# voltage_conditioner.net
KiCad netlist of a schematic drawn in EAGLE
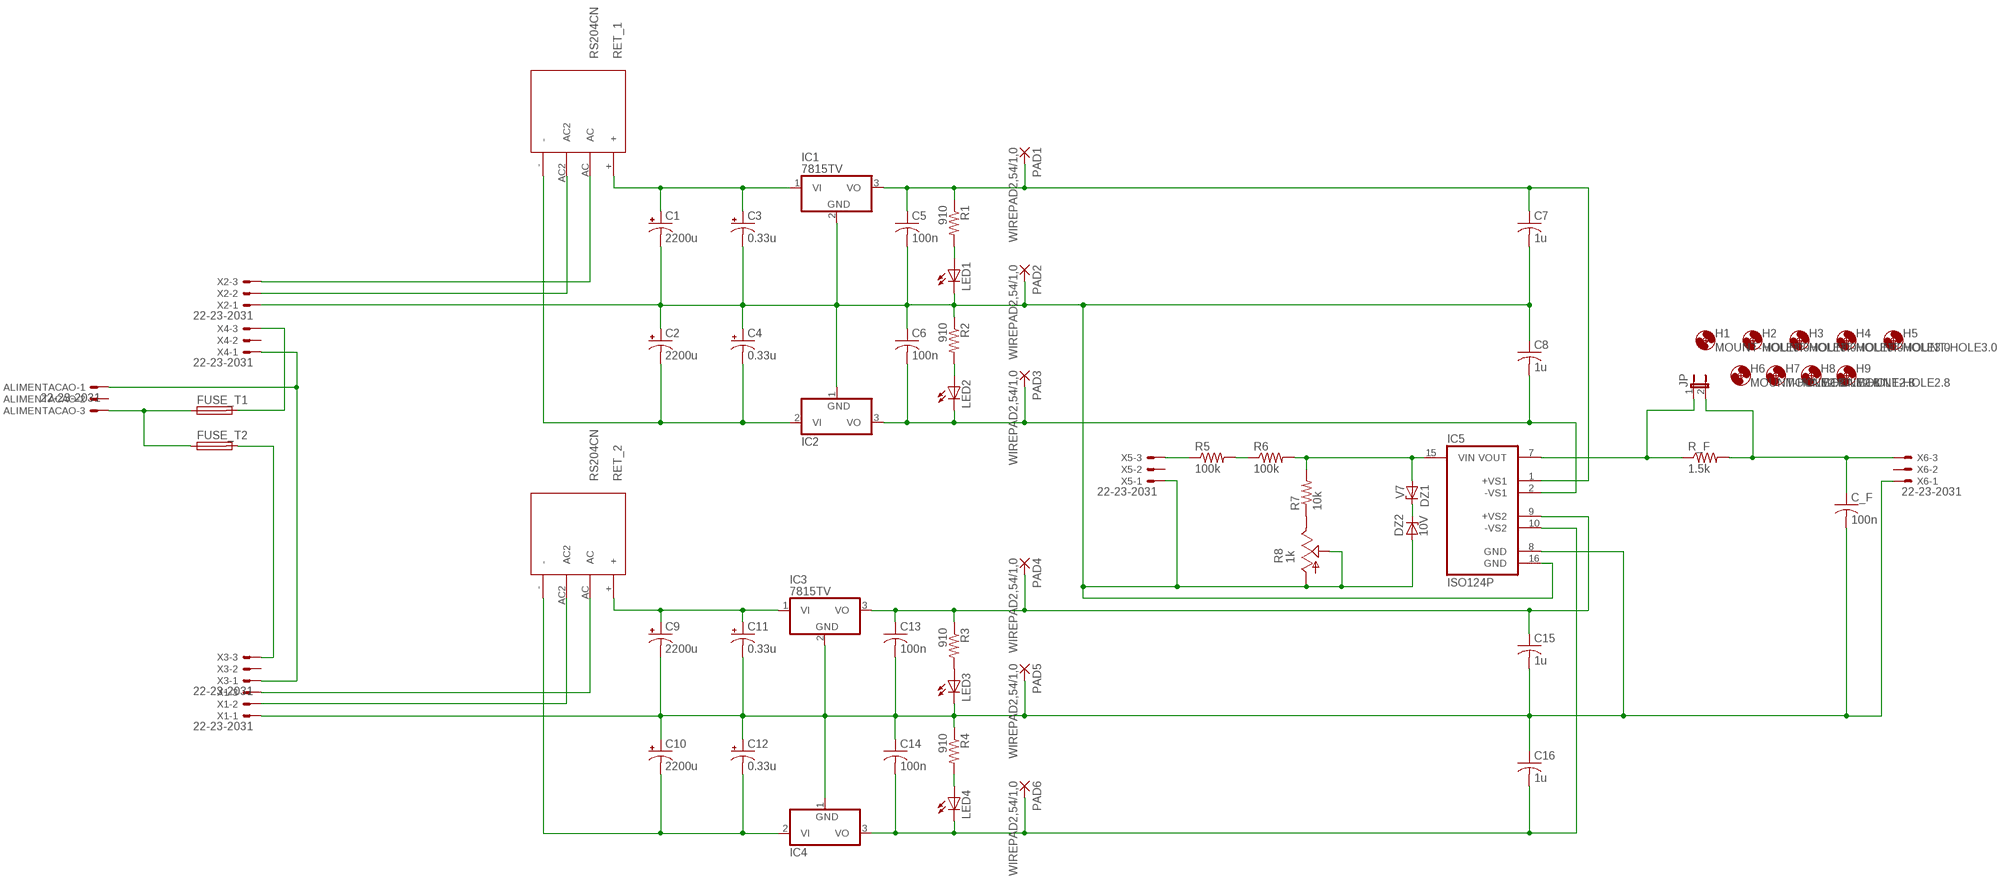
[diagram p0: schematic, sheet 1]

(export (version "E")
  (design (tool "Eeschema 10.0.6"))
  (components
    (comp (ref "ALIMENTACAO")
      (value "22-23-2031")
      (footprint "eagle-import:22-23-2031")
      (fields (field (name "MF") "MOLEX"))
      (libsource (lib "eagle-import") (part "22-23-2031"))
    )
    (comp (ref "C1")
      (value "2200u")
      (footprint "eagle-import:E5-10,5")
      (libsource (lib "eagle-import") (part "CPOL-USE5-10.5"))
    )
    (comp (ref "C2")
      (value "2200u")
      (footprint "eagle-import:E5-10,5")
      (libsource (lib "eagle-import") (part "CPOL-USE5-10.5"))
    )
    (comp (ref "C3")
      (value "0.33u")
      (footprint "eagle-import:E2,5-5")
      (libsource (lib "eagle-import") (part "CPOL-USE2.5-5"))
    )
    (comp (ref "C4")
      (value "0.33u")
      (footprint "eagle-import:E2,5-5")
      (libsource (lib "eagle-import") (part "CPOL-USE2.5-5"))
    )
    (comp (ref "C5")
      (value "100n")
      (footprint "eagle-import:C050-025X075")
      (libsource (lib "eagle-import") (part "C-US050-025X075"))
    )
    (comp (ref "C6")
      (value "100n")
      (footprint "eagle-import:C050-025X075")
      (libsource (lib "eagle-import") (part "C-US050-025X075"))
    )
    (comp (ref "C7")
      (value "1u")
      (footprint "eagle-import:C025-025X050")
      (libsource (lib "eagle-import") (part "C-US025-025X050"))
    )
    (comp (ref "C8")
      (value "1u")
      (footprint "eagle-import:C025-025X050")
      (libsource (lib "eagle-import") (part "C-US025-025X050"))
    )
    (comp (ref "C9")
      (value "2200u")
      (footprint "eagle-import:E5-10,5")
      (libsource (lib "eagle-import") (part "CPOL-USE5-10.5"))
    )
    (comp (ref "C10")
      (value "2200u")
      (footprint "eagle-import:E5-10,5")
      (libsource (lib "eagle-import") (part "CPOL-USE5-10.5"))
    )
    (comp (ref "C11")
      (value "0.33u")
      (footprint "eagle-import:E2,5-5")
      (libsource (lib "eagle-import") (part "CPOL-USE2.5-5"))
    )
    (comp (ref "C12")
      (value "0.33u")
      (footprint "eagle-import:E2,5-5")
      (libsource (lib "eagle-import") (part "CPOL-USE2.5-5"))
    )
    (comp (ref "C13")
      (value "100n")
      (footprint "eagle-import:C050-025X075")
      (libsource (lib "eagle-import") (part "C-US050-025X075"))
    )
    (comp (ref "C14")
      (value "100n")
      (footprint "eagle-import:C050-025X075")
      (libsource (lib "eagle-import") (part "C-US050-025X075"))
    )
    (comp (ref "C15")
      (value "1u")
      (footprint "eagle-import:C025-025X050")
      (libsource (lib "eagle-import") (part "C-US025-025X050"))
    )
    (comp (ref "C16")
      (value "1u")
      (footprint "eagle-import:C025-025X050")
      (libsource (lib "eagle-import") (part "C-US025-025X050"))
    )
    (comp (ref "C_F")
      (value "100n")
      (footprint "eagle-import:C050-025X075")
      (libsource (lib "eagle-import") (part "C-US050-025X075"))
    )
    (comp (ref "DZ1")
      (value "V7")
      (footprint "eagle-import:DO35Z10")
      (libsource (lib "eagle-import") (part "ZENER-DIODEDO35Z10"))
    )
    (comp (ref "DZ2")
      (value "10V")
      (footprint "eagle-import:DO35Z10")
      (libsource (lib "eagle-import") (part "ZENER-DIODEDO35Z10"))
    )
    (comp (ref "FUSE_T1")
      (value "GSH15")
      (footprint "eagle-import:GSH15")
      (fields (field (name "MPN") "64900001039"))
      (libsource (lib "eagle-import") (part "GSH15"))
    )
    (comp (ref "FUSE_T2")
      (value "GSH15")
      (footprint "eagle-import:GSH15")
      (fields (field (name "MPN") "64900001039"))
      (libsource (lib "eagle-import") (part "GSH15"))
    )
    (comp (ref "H1")
      (value "MOUNT-HOLE3.0")
      (footprint "eagle-import:3,0")
      (libsource (lib "eagle-import") (part "MOUNT-HOLE3.0"))
    )
    (comp (ref "H2")
      (value "MOUNT-HOLE3.0")
      (footprint "eagle-import:3,0")
      (libsource (lib "eagle-import") (part "MOUNT-HOLE3.0"))
    )
    (comp (ref "H3")
      (value "MOUNT-HOLE3.0")
      (footprint "eagle-import:3,0")
      (libsource (lib "eagle-import") (part "MOUNT-HOLE3.0"))
    )
    (comp (ref "H4")
      (value "MOUNT-HOLE3.0")
      (footprint "eagle-import:3,0")
      (libsource (lib "eagle-import") (part "MOUNT-HOLE3.0"))
    )
    (comp (ref "H5")
      (value "MOUNT-HOLE3.0")
      (footprint "eagle-import:3,0")
      (libsource (lib "eagle-import") (part "MOUNT-HOLE3.0"))
    )
    (comp (ref "H6")
      (value "MOUNT-HOLE2.8")
      (footprint "eagle-import:2,8")
      (libsource (lib "eagle-import") (part "MOUNT-HOLE2.8"))
    )
    (comp (ref "H7")
      (value "MOUNT-HOLE2.8")
      (footprint "eagle-import:2,8")
      (libsource (lib "eagle-import") (part "MOUNT-HOLE2.8"))
    )
    (comp (ref "H8")
      (value "MOUNT-HOLE2.8")
      (footprint "eagle-import:2,8")
      (libsource (lib "eagle-import") (part "MOUNT-HOLE2.8"))
    )
    (comp (ref "H9")
      (value "MOUNT-HOLE2.8")
      (footprint "eagle-import:2,8")
      (libsource (lib "eagle-import") (part "MOUNT-HOLE2.8"))
    )
    (comp (ref "IC1")
      (value "7815TV")
      (footprint "eagle-import:TO220V")
      (libsource (lib "eagle-import") (part "78TV15"))
    )
    (comp (ref "IC2")
      (value "7915C")
      (footprint "eagle-import:TO220V")
      (libsource (lib "eagle-import") (part "7915C"))
    )
    (comp (ref "IC3")
      (value "7815TV")
      (footprint "eagle-import:TO220V")
      (libsource (lib "eagle-import") (part "78TV15"))
    )
    (comp (ref "IC4")
      (value "7915C")
      (footprint "eagle-import:TO220V")
      (libsource (lib "eagle-import") (part "7915C"))
    )
    (comp (ref "IC5")
      (value "ISO124P")
      (footprint "eagle-import:DIL16_8")
      (fields (field (name "MF") "TEXAS INSTRUMENTS"))
      (libsource (lib "eagle-import") (part "ISO124P"))
    )
    (comp (ref "JP")
      (value "JP1E")
      (footprint "eagle-import:JP1")
      (libsource (lib "eagle-import") (part "JP1E"))
    )
    (comp (ref "LED1")
      (value "LED3MM")
      (footprint "eagle-import:LED3MM")
      (libsource (lib "eagle-import") (part "LED3MM"))
    )
    (comp (ref "LED2")
      (value "LED3MM")
      (footprint "eagle-import:LED3MM")
      (libsource (lib "eagle-import") (part "led_LED3MM"))
    )
    (comp (ref "LED3")
      (value "LED3MM")
      (footprint "eagle-import:LED3MM")
      (libsource (lib "eagle-import") (part "led_LED3MM"))
    )
    (comp (ref "LED4")
      (value "LED3MM")
      (footprint "eagle-import:LED3MM")
      (libsource (lib "eagle-import") (part "led_LED3MM"))
    )
    (comp (ref "PAD1")
      (value "WIREPAD2,54/1,0")
      (footprint "eagle-import:2,54_1,0")
      (libsource (lib "eagle-import") (part "WIREPAD2,54/1,0"))
    )
    (comp (ref "PAD2")
      (value "WIREPAD2,54/1,0")
      (footprint "eagle-import:2,54_1,0")
      (libsource (lib "eagle-import") (part "WIREPAD2,54/1,0"))
    )
    (comp (ref "PAD3")
      (value "WIREPAD2,54/1,0")
      (footprint "eagle-import:2,54_1,0")
      (libsource (lib "eagle-import") (part "WIREPAD2,54/1,0"))
    )
    (comp (ref "PAD4")
      (value "WIREPAD2,54/1,0")
      (footprint "eagle-import:2,54_1,0")
      (libsource (lib "eagle-import") (part "WIREPAD2,54/1,0"))
    )
    (comp (ref "PAD5")
      (value "WIREPAD2,54/1,0")
      (footprint "eagle-import:2,54_1,0")
      (libsource (lib "eagle-import") (part "WIREPAD2,54/1,0"))
    )
    (comp (ref "PAD6")
      (value "WIREPAD2,54/1,0")
      (footprint "eagle-import:2,54_1,0")
      (libsource (lib "eagle-import") (part "WIREPAD2,54/1,0"))
    )
    (comp (ref "R1")
      (value "910")
      (footprint "eagle-import:0207_7")
      (libsource (lib "eagle-import") (part "R-US_0207/7"))
    )
    (comp (ref "R2")
      (value "910")
      (footprint "eagle-import:0207_7")
      (libsource (lib "eagle-import") (part "R-US_0207/7"))
    )
    (comp (ref "R3")
      (value "910")
      (footprint "eagle-import:0207_7")
      (libsource (lib "eagle-import") (part "R-US_0207/7"))
    )
    (comp (ref "R4")
      (value "910")
      (footprint "eagle-import:0207_7")
      (libsource (lib "eagle-import") (part "R-US_0207/7"))
    )
    (comp (ref "R5")
      (value "100k")
      (footprint "eagle-import:0204_7")
      (libsource (lib "eagle-import") (part "R-US_0204/7"))
    )
    (comp (ref "R6")
      (value "100k")
      (footprint "eagle-import:0204_7")
      (libsource (lib "eagle-import") (part "R-US_0204/7"))
    )
    (comp (ref "R7")
      (value "10k")
      (footprint "eagle-import:0204_7")
      (libsource (lib "eagle-import") (part "R-US_0204/7"))
    )
    (comp (ref "R8")
      (value "1k")
      (footprint "eagle-import:RS3")
      (libsource (lib "eagle-import") (part "TRIM_US-RS3"))
    )
    (comp (ref "RET_1")
      (value "RS204CN")
      (footprint "eagle-import:SIP")
      (libsource (lib "eagle-import") (part "RS204CN"))
    )
    (comp (ref "RET_2")
      (value "RS204CN")
      (footprint "eagle-import:SIP")
      (libsource (lib "eagle-import") (part "RS204CN"))
    )
    (comp (ref "R_F")
      (value "1.5k")
      (footprint "eagle-import:0204_7")
      (libsource (lib "eagle-import") (part "R-US_0204/7"))
    )
    (comp (ref "X1")
      (value "22-23-2031")
      (footprint "eagle-import:22-23-2031")
      (fields (field (name "MF") "MOLEX"))
      (libsource (lib "eagle-import") (part "22-23-2031"))
    )
    (comp (ref "X2")
      (value "22-23-2031")
      (footprint "eagle-import:22-23-2031")
      (fields (field (name "MF") "MOLEX"))
      (libsource (lib "eagle-import") (part "22-23-2031"))
    )
    (comp (ref "X3")
      (value "22-23-2031")
      (footprint "eagle-import:22-23-2031")
      (fields (field (name "MF") "MOLEX"))
      (libsource (lib "eagle-import") (part "22-23-2031"))
    )
    (comp (ref "X4")
      (value "22-23-2031")
      (footprint "eagle-import:22-23-2031")
      (fields (field (name "MF") "MOLEX"))
      (libsource (lib "eagle-import") (part "22-23-2031"))
    )
    (comp (ref "X5")
      (value "22-23-2031")
      (footprint "eagle-import:22-23-2031")
      (fields (field (name "MF") "MOLEX"))
      (libsource (lib "eagle-import") (part "22-23-2031"))
    )
    (comp (ref "X6")
      (value "22-23-2031")
      (footprint "eagle-import:22-23-2031")
      (fields (field (name "MF") "MOLEX"))
      (libsource (lib "eagle-import") (part "22-23-2031"))
    )
  )
  (nets
    (net (code "1") (name "Net-(ALIMENTACAOA-S)") (class "Default")
      (node (ref "ALIMENTACAO") (pin "1") (pinfunction "S_1") (pintype "passive"))
      (node (ref "X3") (pin "1") (pinfunction "S_1") (pintype "passive"))
      (node (ref "X4") (pin "1") (pinfunction "S_1") (pintype "passive"))
    )
    (net (code "2") (name "Net-(ALIMENTACAOC-S)") (class "Default")
      (node (ref "ALIMENTACAO") (pin "3") (pinfunction "S_3") (pintype "passive"))
      (node (ref "FUSE_T1") (pin "1") (pinfunction "1_1") (pintype "passive"))
      (node (ref "FUSE_T2") (pin "1") (pinfunction "1_1") (pintype "passive"))
    )
    (net (code "3") (name "Net-(DZ1-PadC)") (class "Default")
      (node (ref "DZ1") (pin "C") (pinfunction "C_C") (pintype "passive"))
      (node (ref "DZ2") (pin "C") (pinfunction "C_C") (pintype "passive"))
    )
    (net (code "4") (name "Net-(IC1-GND)") (class "Default")
      (node (ref "C1") (pin "-") (pinfunction "-_-") (pintype "passive"))
      (node (ref "C2") (pin "+") (pinfunction "+_+") (pintype "passive"))
      (node (ref "C3") (pin "-") (pinfunction "-_-") (pintype "passive"))
      (node (ref "C4") (pin "+") (pinfunction "+_+") (pintype "passive"))
      (node (ref "C5") (pin "2") (pinfunction "2_2") (pintype "passive"))
      (node (ref "C6") (pin "1") (pinfunction "1_1") (pintype "passive"))
      (node (ref "C7") (pin "2") (pinfunction "2_2") (pintype "passive"))
      (node (ref "C8") (pin "1") (pinfunction "1_1") (pintype "passive"))
      (node (ref "DZ2") (pin "A") (pinfunction "A_A") (pintype "passive"))
      (node (ref "IC1") (pin "2") (pinfunction "GND_2") (pintype "passive"))
      (node (ref "IC2") (pin "1") (pinfunction "GND_1") (pintype "passive"))
      (node (ref "IC5") (pin "16") (pinfunction "GND_16") (pintype "power_in"))
      (node (ref "LED1") (pin "K") (pinfunction "C_K") (pintype "passive"))
      (node (ref "PAD2") (pin "1") (pinfunction "P_1") (pintype "passive"))
      (node (ref "R2") (pin "1") (pinfunction "1_1") (pintype "passive"))
      (node (ref "R8") (pin "A") (pinfunction "A_A") (pintype "passive"))
      (node (ref "R8") (pin "S") (pinfunction "S_S") (pintype "passive"))
      (node (ref "X2") (pin "1") (pinfunction "S_1") (pintype "passive"))
      (node (ref "X5") (pin "1") (pinfunction "S_1") (pintype "passive"))
    )
    (net (code "5") (name "Net-(IC1-VI)") (class "Default")
      (node (ref "C1") (pin "+") (pinfunction "+_+") (pintype "passive"))
      (node (ref "C3") (pin "+") (pinfunction "+_+") (pintype "passive"))
      (node (ref "IC1") (pin "1") (pinfunction "VI_1") (pintype "input"))
      (node (ref "RET_1") (pin "+") (pinfunction "+_+") (pintype "bidirectional"))
    )
    (net (code "6") (name "Net-(IC1-VO)") (class "Default")
      (node (ref "C5") (pin "1") (pinfunction "1_1") (pintype "passive"))
      (node (ref "C7") (pin "1") (pinfunction "1_1") (pintype "passive"))
      (node (ref "IC1") (pin "3") (pinfunction "VO_3") (pintype "passive"))
      (node (ref "IC5") (pin "1") (pinfunction "+VS1_1") (pintype "power_in"))
      (node (ref "PAD1") (pin "1") (pinfunction "P_1") (pintype "passive"))
      (node (ref "R1") (pin "1") (pinfunction "1_1") (pintype "passive"))
    )
    (net (code "7") (name "Net-(IC2-VI)") (class "Default")
      (node (ref "C2") (pin "-") (pinfunction "-_-") (pintype "passive"))
      (node (ref "C4") (pin "-") (pinfunction "-_-") (pintype "passive"))
      (node (ref "IC2") (pin "2") (pinfunction "VI_2") (pintype "input"))
      (node (ref "RET_1") (pin "-") (pinfunction "-_-") (pintype "bidirectional"))
    )
    (net (code "8") (name "Net-(IC2-VO)") (class "Default")
      (node (ref "C6") (pin "2") (pinfunction "2_2") (pintype "passive"))
      (node (ref "C8") (pin "2") (pinfunction "2_2") (pintype "passive"))
      (node (ref "IC2") (pin "3") (pinfunction "VO_3") (pintype "passive"))
      (node (ref "IC5") (pin "2") (pinfunction "-VS1_2") (pintype "power_in"))
      (node (ref "LED2") (pin "K") (pinfunction "C_K") (pintype "passive"))
      (node (ref "PAD3") (pin "1") (pinfunction "P_1") (pintype "passive"))
    )
    (net (code "9") (name "Net-(IC3-GND)") (class "Default")
      (node (ref "C10") (pin "+") (pinfunction "+_+") (pintype "passive"))
      (node (ref "C11") (pin "-") (pinfunction "-_-") (pintype "passive"))
      (node (ref "C12") (pin "+") (pinfunction "+_+") (pintype "passive"))
      (node (ref "C13") (pin "2") (pinfunction "2_2") (pintype "passive"))
      (node (ref "C14") (pin "1") (pinfunction "1_1") (pintype "passive"))
      (node (ref "C15") (pin "2") (pinfunction "2_2") (pintype "passive"))
      (node (ref "C16") (pin "1") (pinfunction "1_1") (pintype "passive"))
      (node (ref "C9") (pin "-") (pinfunction "-_-") (pintype "passive"))
      (node (ref "C_F") (pin "2") (pinfunction "2_2") (pintype "passive"))
      (node (ref "IC3") (pin "2") (pinfunction "GND_2") (pintype "passive"))
      (node (ref "IC4") (pin "1") (pinfunction "GND_1") (pintype "passive"))
      (node (ref "IC5") (pin "8") (pinfunction "GND_8") (pintype "power_in"))
      (node (ref "LED3") (pin "K") (pinfunction "C_K") (pintype "passive"))
      (node (ref "PAD5") (pin "1") (pinfunction "P_1") (pintype "passive"))
      (node (ref "R4") (pin "1") (pinfunction "1_1") (pintype "passive"))
      (node (ref "X1") (pin "1") (pinfunction "S_1") (pintype "passive"))
      (node (ref "X6") (pin "1") (pinfunction "S_1") (pintype "passive"))
    )
    (net (code "10") (name "Net-(IC3-VI)") (class "Default")
      (node (ref "C11") (pin "+") (pinfunction "+_+") (pintype "passive"))
      (node (ref "C9") (pin "+") (pinfunction "+_+") (pintype "passive"))
      (node (ref "IC3") (pin "1") (pinfunction "VI_1") (pintype "input"))
      (node (ref "RET_2") (pin "+") (pinfunction "+_+") (pintype "bidirectional"))
    )
    (net (code "11") (name "Net-(IC3-VO)") (class "Default")
      (node (ref "C13") (pin "1") (pinfunction "1_1") (pintype "passive"))
      (node (ref "C15") (pin "1") (pinfunction "1_1") (pintype "passive"))
      (node (ref "IC3") (pin "3") (pinfunction "VO_3") (pintype "passive"))
      (node (ref "IC5") (pin "9") (pinfunction "+VS2_9") (pintype "power_in"))
      (node (ref "PAD4") (pin "1") (pinfunction "P_1") (pintype "passive"))
      (node (ref "R3") (pin "1") (pinfunction "1_1") (pintype "passive"))
    )
    (net (code "12") (name "Net-(IC4-VI)") (class "Default")
      (node (ref "C10") (pin "-") (pinfunction "-_-") (pintype "passive"))
      (node (ref "C12") (pin "-") (pinfunction "-_-") (pintype "passive"))
      (node (ref "IC4") (pin "2") (pinfunction "VI_2") (pintype "input"))
      (node (ref "RET_2") (pin "-") (pinfunction "-_-") (pintype "bidirectional"))
    )
    (net (code "13") (name "Net-(IC4-VO)") (class "Default")
      (node (ref "C14") (pin "2") (pinfunction "2_2") (pintype "passive"))
      (node (ref "C16") (pin "2") (pinfunction "2_2") (pintype "passive"))
      (node (ref "IC4") (pin "3") (pinfunction "VO_3") (pintype "passive"))
      (node (ref "IC5") (pin "10") (pinfunction "-VS2_10") (pintype "power_in"))
      (node (ref "LED4") (pin "K") (pinfunction "C_K") (pintype "passive"))
      (node (ref "PAD6") (pin "1") (pinfunction "P_1") (pintype "passive"))
    )
    (net (code "14") (name "Net-(IC5-VIN)") (class "Default")
      (node (ref "DZ1") (pin "A") (pinfunction "A_A") (pintype "passive"))
      (node (ref "IC5") (pin "15") (pinfunction "VIN_15") (pintype "input"))
      (node (ref "R6") (pin "2") (pinfunction "2_2") (pintype "passive"))
      (node (ref "R7") (pin "2") (pinfunction "2_2") (pintype "passive"))
    )
    (net (code "15") (name "Net-(IC5-VOUT)") (class "Default")
      (node (ref "IC5") (pin "7") (pinfunction "VOUT_7") (pintype "output"))
      (node (ref "JP") (pin "1") (pinfunction "1_1") (pintype "passive"))
      (node (ref "R_F") (pin "1") (pinfunction "1_1") (pintype "passive"))
    )
    (net (code "16") (name "Net-(LED1-PadA)") (class "Default")
      (node (ref "LED1") (pin "A") (pinfunction "A_A") (pintype "passive"))
      (node (ref "R1") (pin "2") (pinfunction "2_2") (pintype "passive"))
    )
    (net (code "17") (name "Net-(LED2-PadA)") (class "Default")
      (node (ref "LED2") (pin "A") (pinfunction "A_A") (pintype "passive"))
      (node (ref "R2") (pin "2") (pinfunction "2_2") (pintype "passive"))
    )
    (net (code "18") (name "Net-(LED3-PadA)") (class "Default")
      (node (ref "LED3") (pin "A") (pinfunction "A_A") (pintype "passive"))
      (node (ref "R3") (pin "2") (pinfunction "2_2") (pintype "passive"))
    )
    (net (code "19") (name "Net-(LED4-PadA)") (class "Default")
      (node (ref "LED4") (pin "A") (pinfunction "A_A") (pintype "passive"))
      (node (ref "R4") (pin "2") (pinfunction "2_2") (pintype "passive"))
    )
    (net (code "20") (name "Net-(R5-Pad2)") (class "Default")
      (node (ref "R5") (pin "2") (pinfunction "2_2") (pintype "passive"))
      (node (ref "R6") (pin "1") (pinfunction "1_1") (pintype "passive"))
    )
    (net (code "21") (name "Net-(R7-Pad1)") (class "Default")
      (node (ref "R7") (pin "1") (pinfunction "1_1") (pintype "passive"))
      (node (ref "R8") (pin "E") (pinfunction "E_E") (pintype "passive"))
    )
    (net (code "22") (name "Net-(X1B-S)") (class "Default")
      (node (ref "RET_2") (pin "AC2") (pinfunction "AC2_AC2") (pintype "bidirectional"))
      (node (ref "X1") (pin "2") (pinfunction "S_2") (pintype "passive"))
    )
    (net (code "23") (name "Net-(X1C-S)") (class "Default")
      (node (ref "RET_2") (pin "AC") (pinfunction "AC_AC") (pintype "bidirectional"))
      (node (ref "X1") (pin "3") (pinfunction "S_3") (pintype "passive"))
    )
    (net (code "24") (name "Net-(X2B-S)") (class "Default")
      (node (ref "RET_1") (pin "AC2") (pinfunction "AC2_AC2") (pintype "bidirectional"))
      (node (ref "X2") (pin "2") (pinfunction "S_2") (pintype "passive"))
    )
    (net (code "25") (name "Net-(X2C-S)") (class "Default")
      (node (ref "RET_1") (pin "AC") (pinfunction "AC_AC") (pintype "bidirectional"))
      (node (ref "X2") (pin "3") (pinfunction "S_3") (pintype "passive"))
    )
    (net (code "26") (name "Net-(X3C-S)") (class "Default")
      (node (ref "FUSE_T2") (pin "2") (pinfunction "2_2") (pintype "passive"))
      (node (ref "X3") (pin "3") (pinfunction "S_3") (pintype "passive"))
    )
    (net (code "27") (name "Net-(X4C-S)") (class "Default")
      (node (ref "FUSE_T1") (pin "2") (pinfunction "2_2") (pintype "passive"))
      (node (ref "X4") (pin "3") (pinfunction "S_3") (pintype "passive"))
    )
    (net (code "28") (name "Net-(X5C-S)") (class "Default")
      (node (ref "R5") (pin "1") (pinfunction "1_1") (pintype "passive"))
      (node (ref "X5") (pin "3") (pinfunction "S_3") (pintype "passive"))
    )
    (net (code "29") (name "Net-(X6C-S)") (class "Default")
      (node (ref "C_F") (pin "1") (pinfunction "1_1") (pintype "passive"))
      (node (ref "JP") (pin "2") (pinfunction "2_2") (pintype "passive"))
      (node (ref "R_F") (pin "2") (pinfunction "2_2") (pintype "passive"))
      (node (ref "X6") (pin "3") (pinfunction "S_3") (pintype "passive"))
    )
    (net (code "30") (name "unconnected-(ALIMENTACAOB-S-Pad2)") (class "Default")
      (node (ref "ALIMENTACAO") (pin "2") (pinfunction "S_2") (pintype "passive"))
    )
    (net (code "31") (name "unconnected-(X3B-S-Pad2)") (class "Default")
      (node (ref "X3") (pin "2") (pinfunction "S_2") (pintype "passive"))
    )
    (net (code "32") (name "unconnected-(X4B-S-Pad2)") (class "Default")
      (node (ref "X4") (pin "2") (pinfunction "S_2") (pintype "passive"))
    )
    (net (code "33") (name "unconnected-(X5B-S-Pad2)") (class "Default")
      (node (ref "X5") (pin "2") (pinfunction "S_2") (pintype "passive"))
    )
    (net (code "34") (name "unconnected-(X6B-S-Pad2)") (class "Default")
      (node (ref "X6") (pin "2") (pinfunction "S_2") (pintype "passive"))
    )
  )
)
